# regelschaltplan.net
KiCad netlist of a schematic drawn in EAGLE
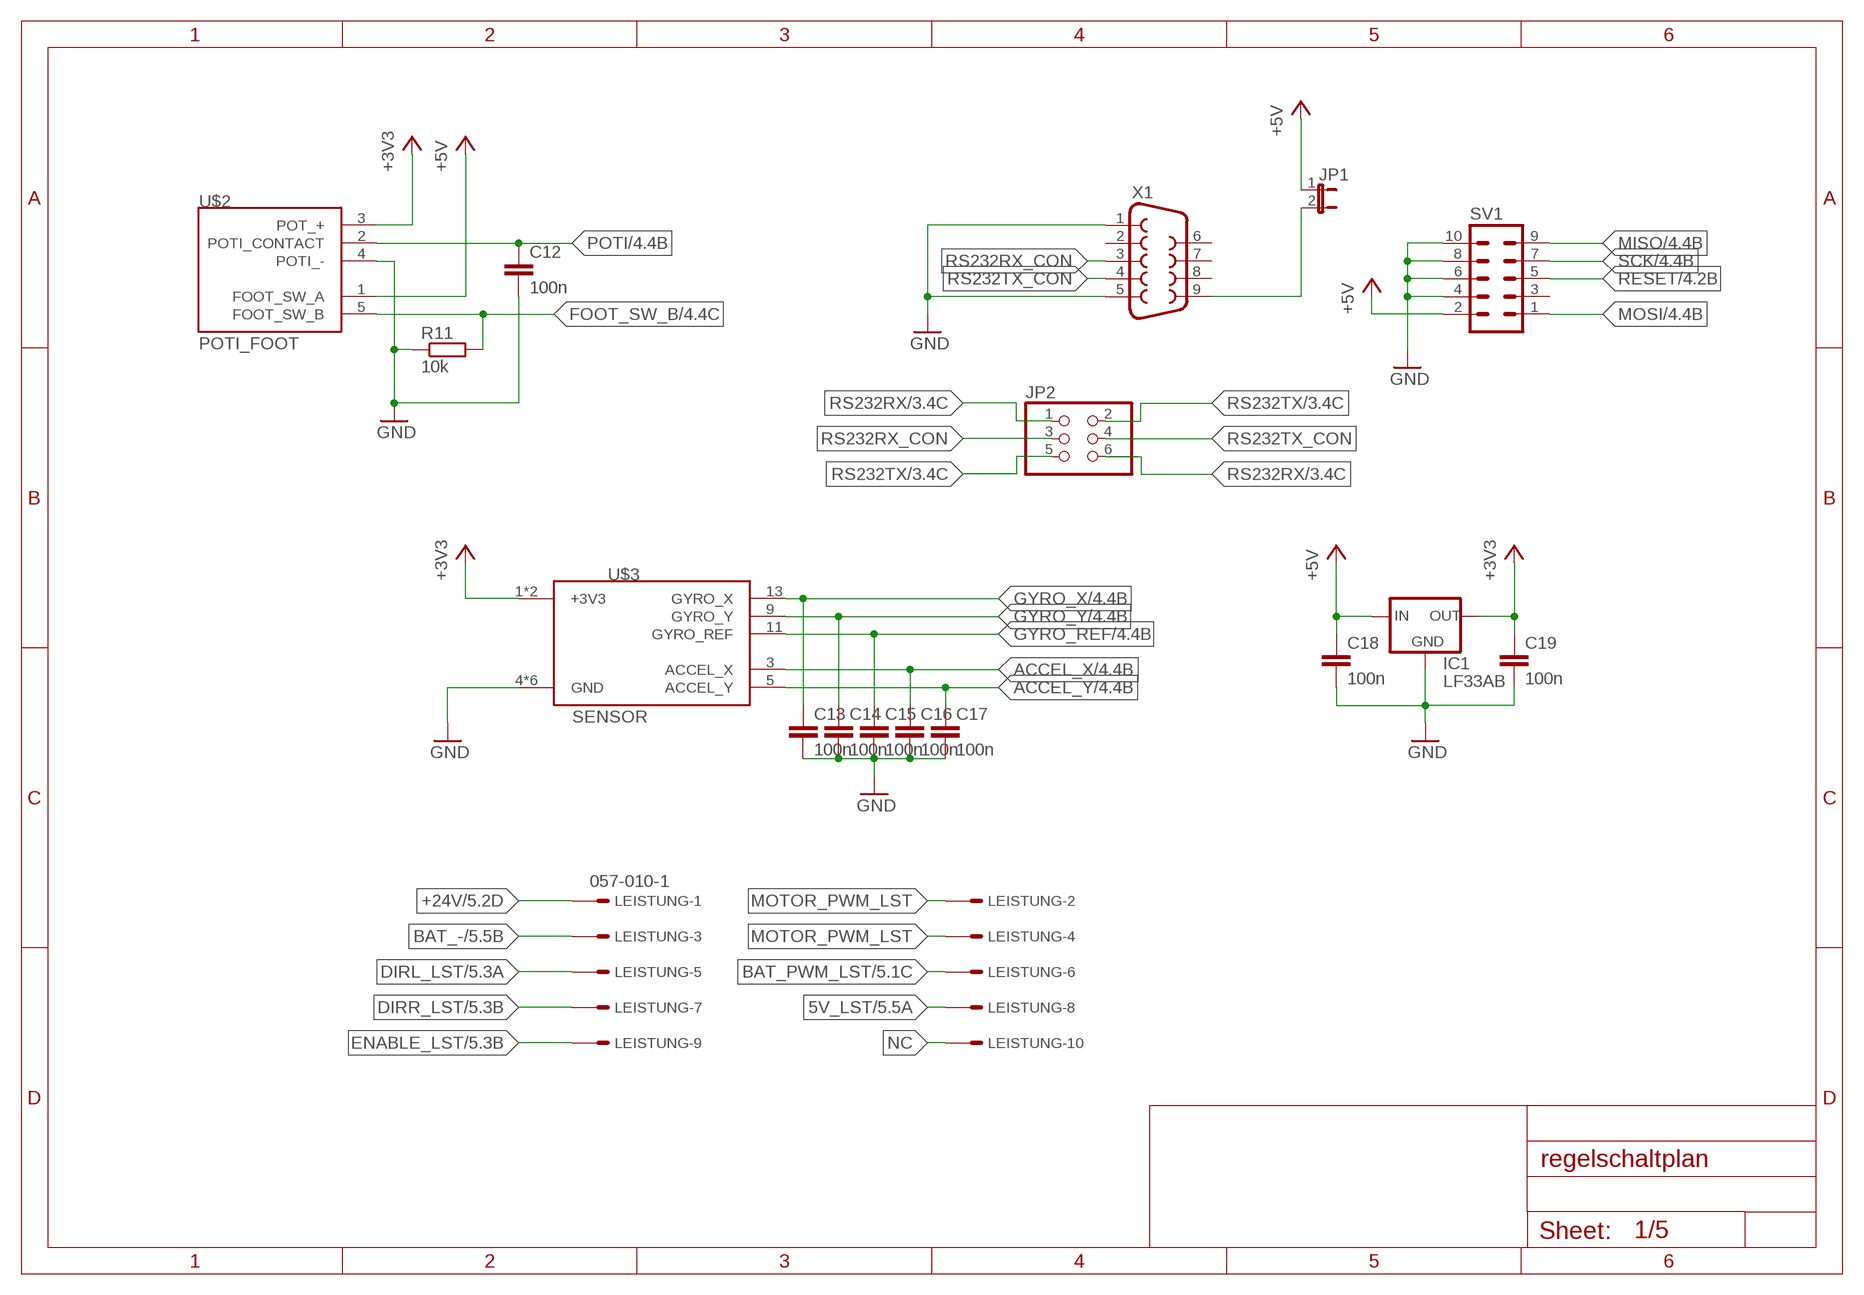
[diagram p0: schematic, sheet 1]
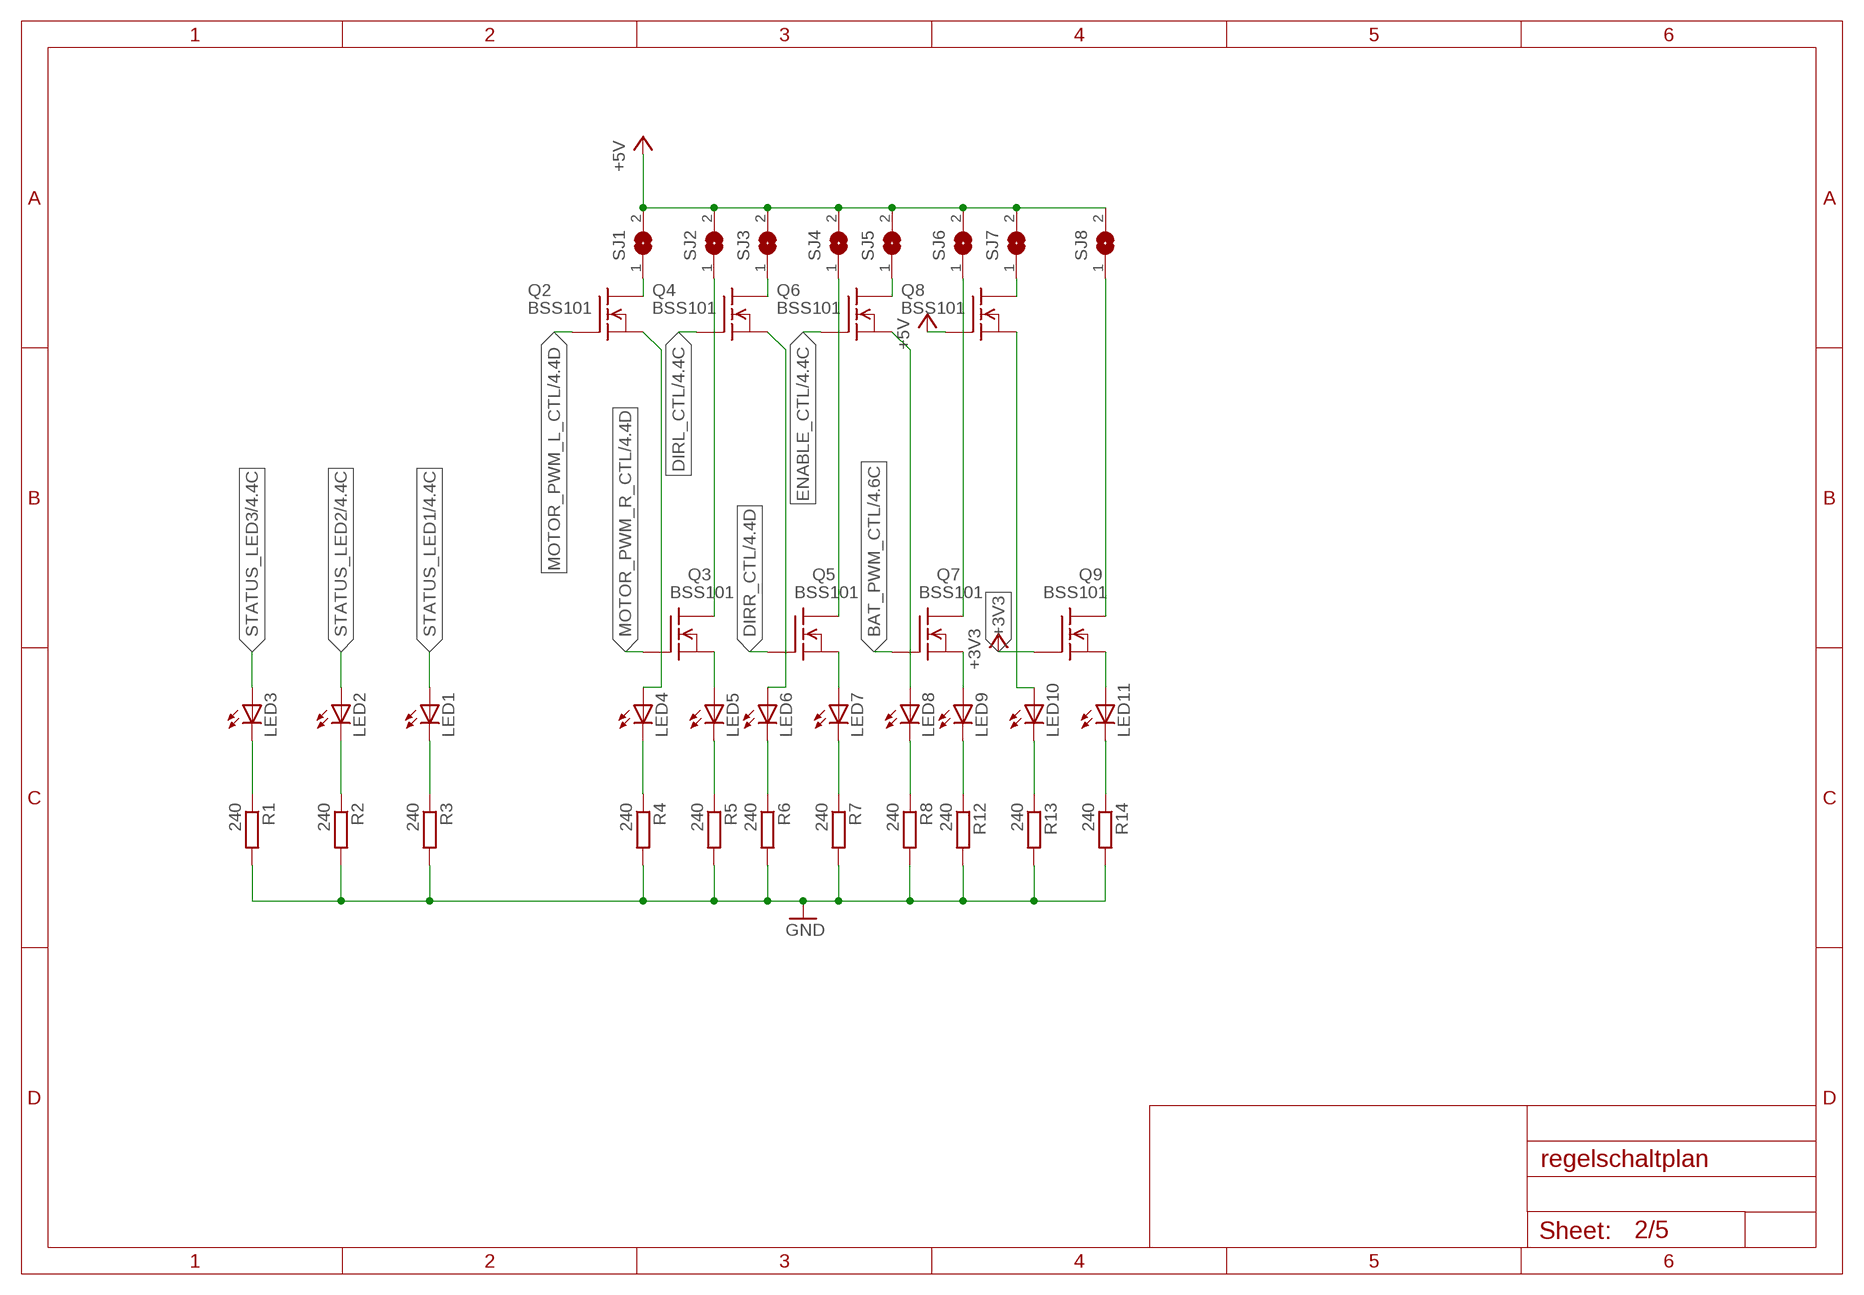
[diagram p1: schematic, sheet 2]
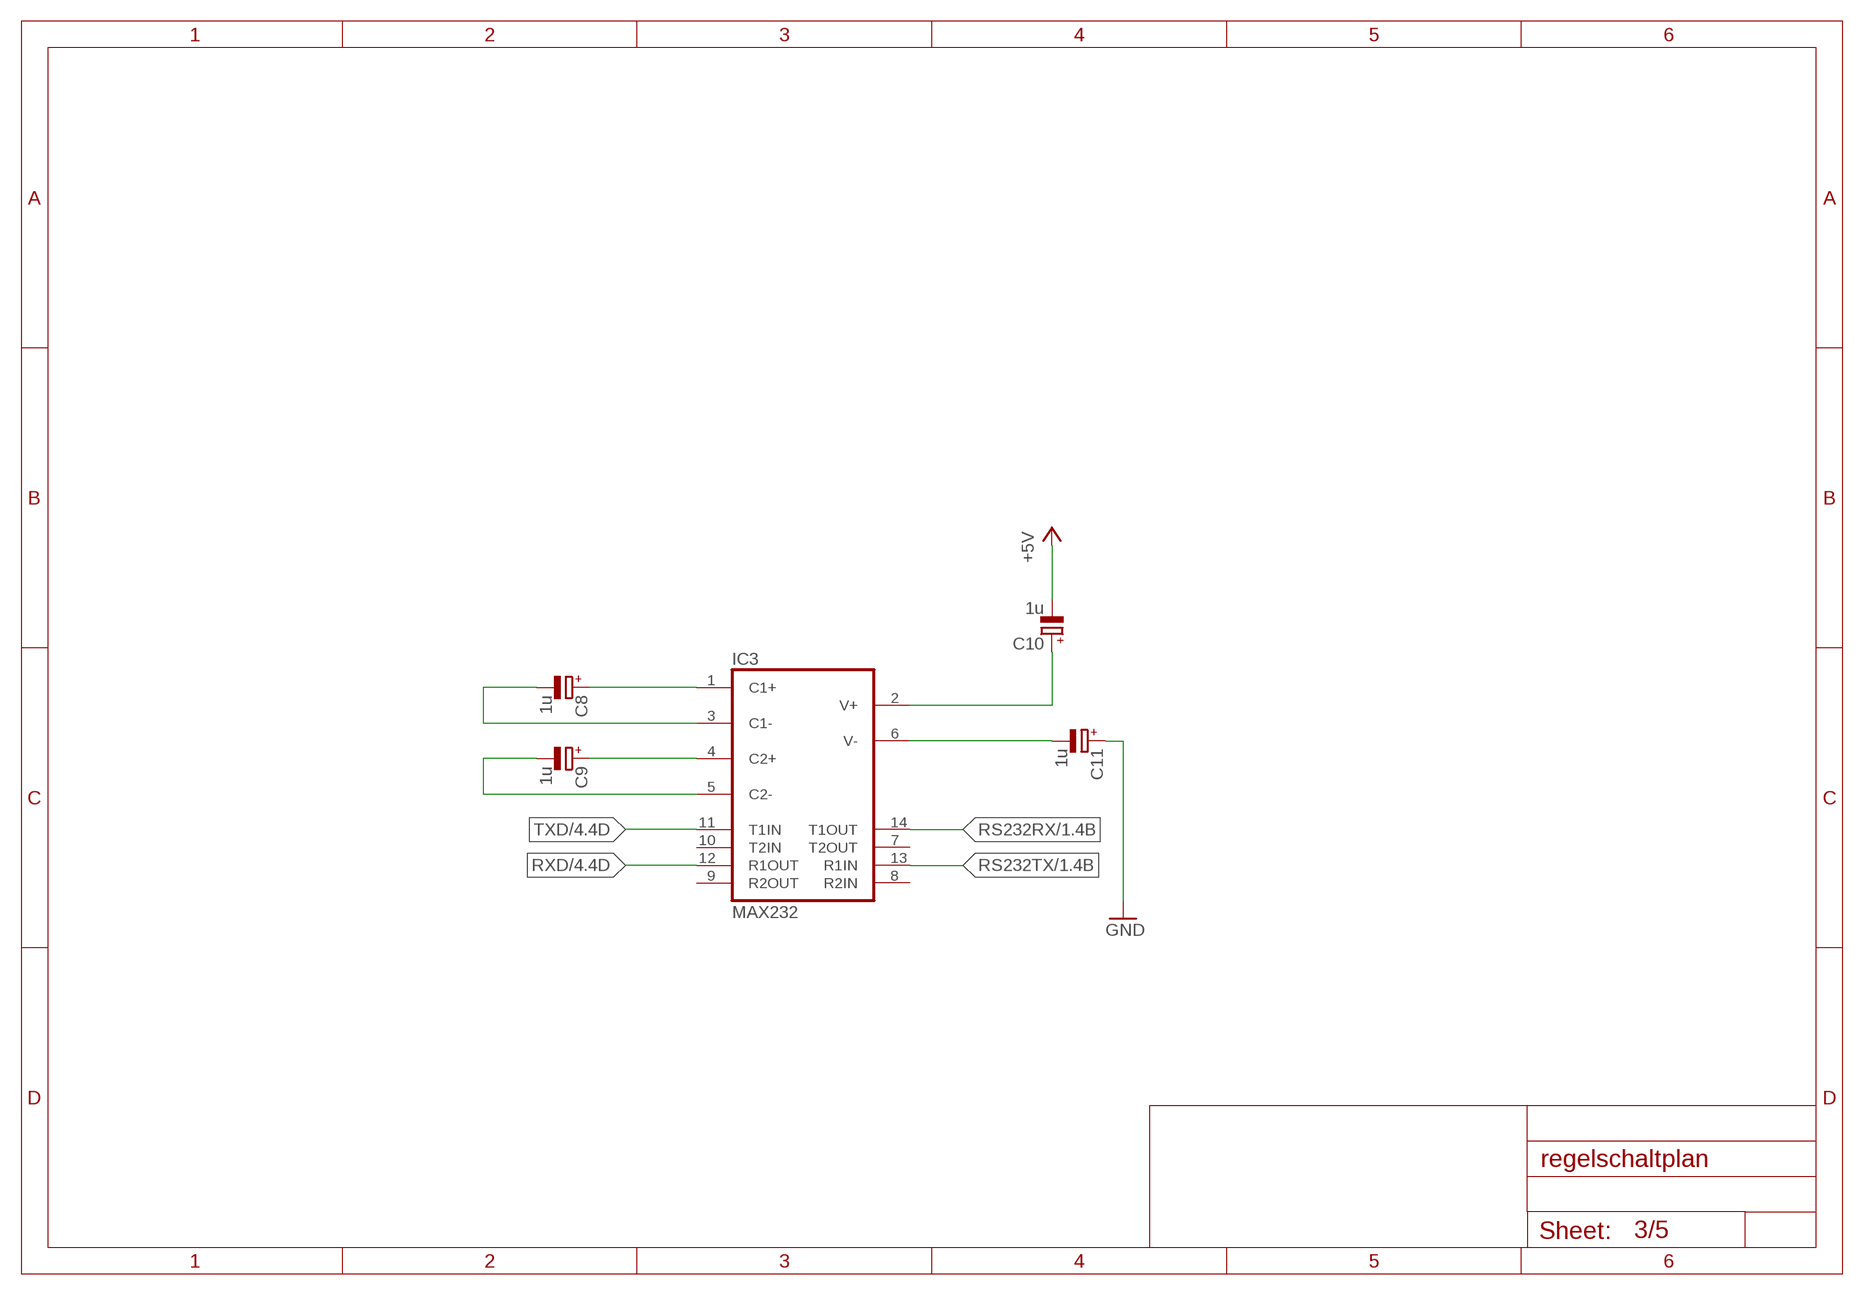
[diagram p2: schematic, sheet 3]
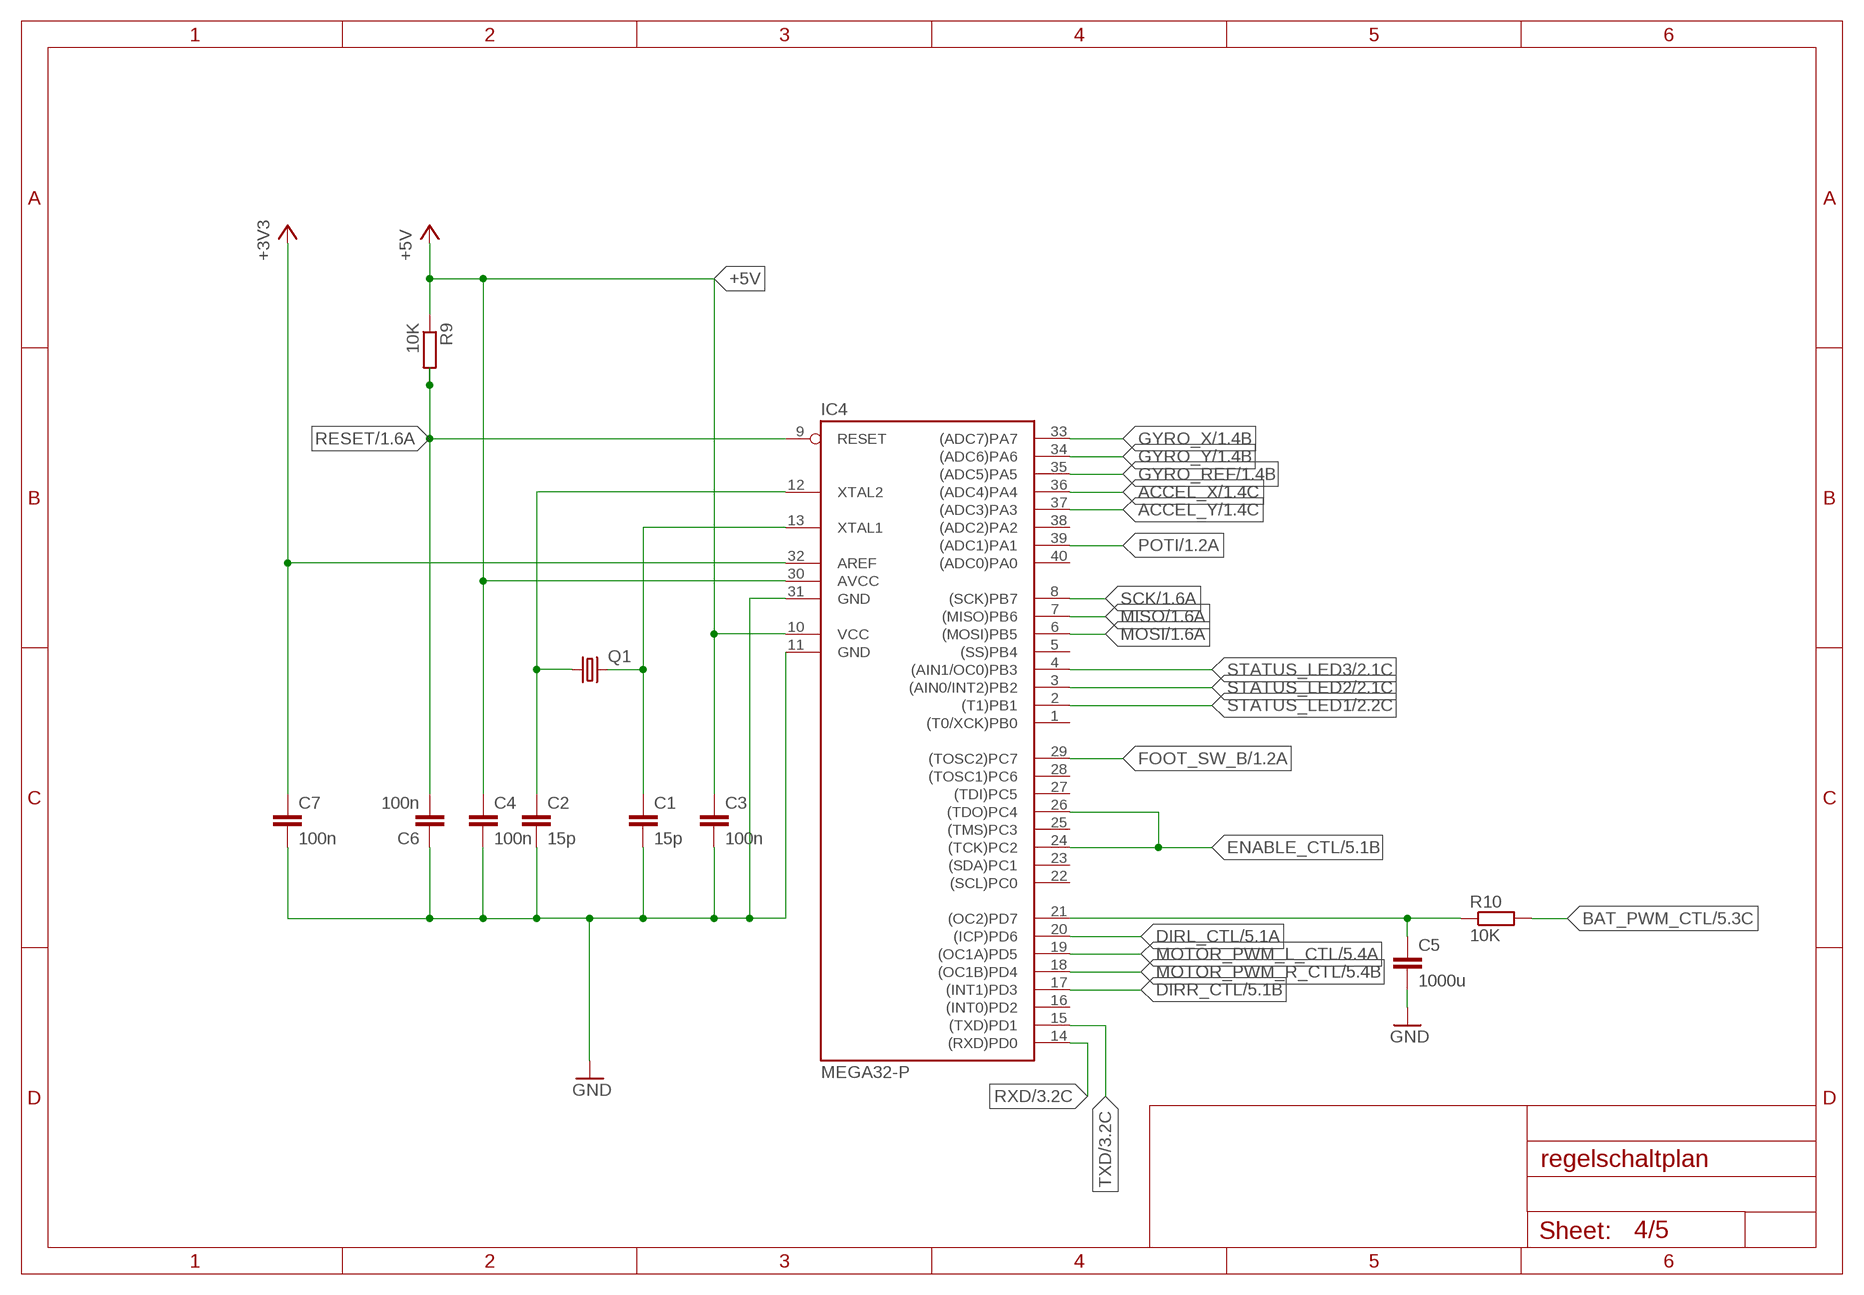
[diagram p3: schematic, sheet 4]
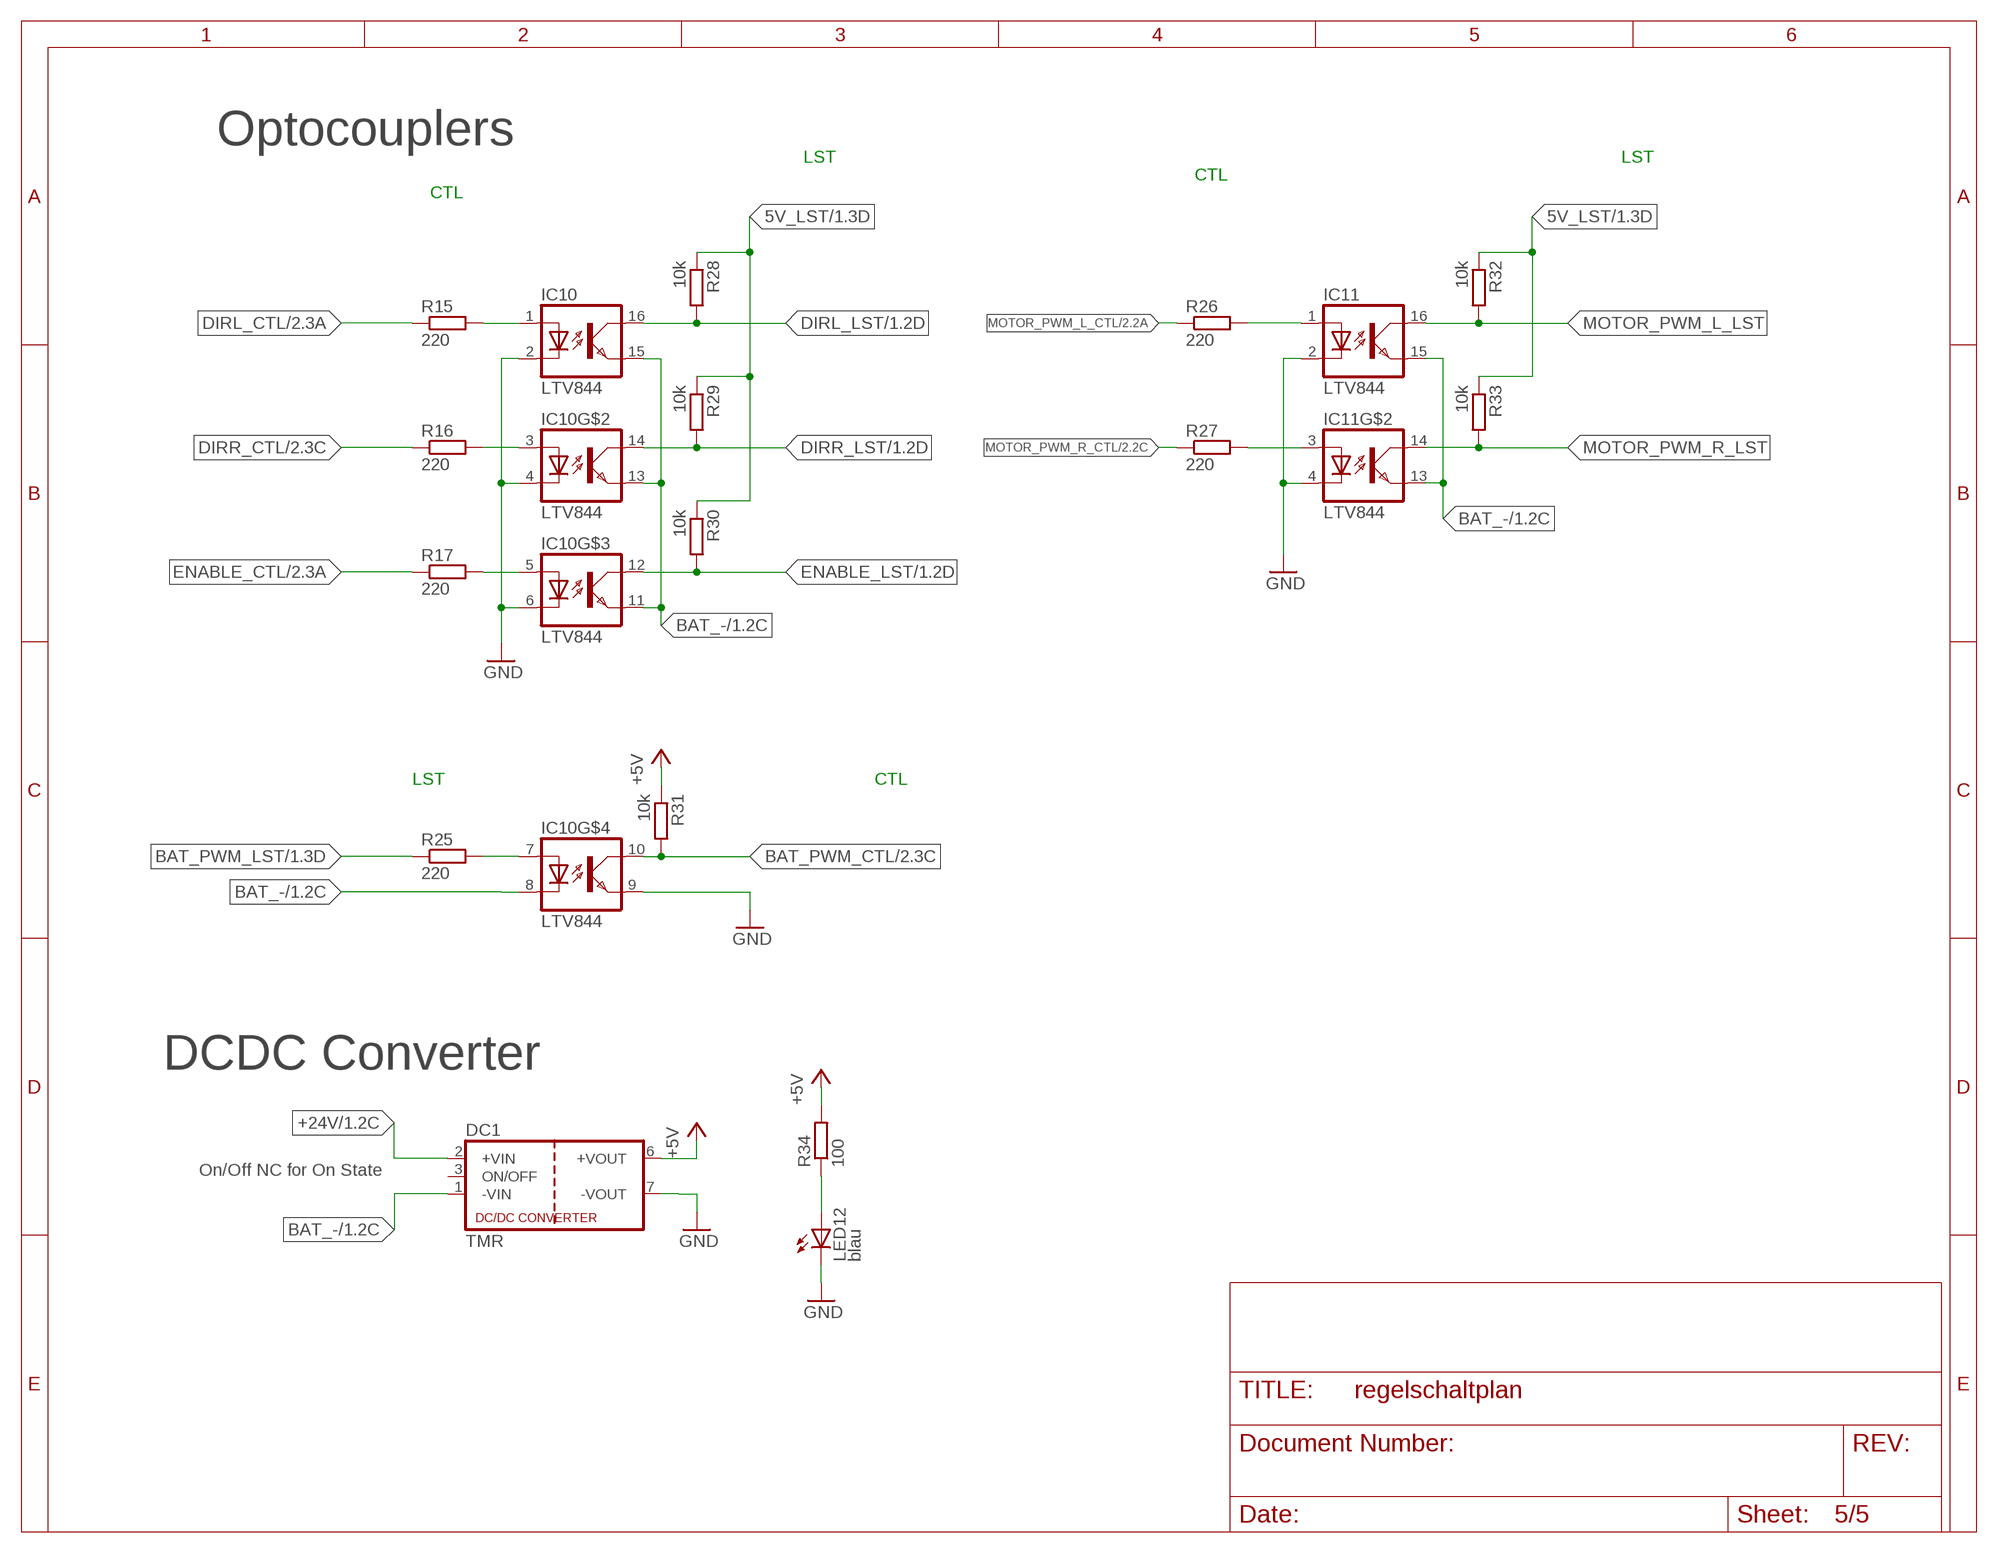
[diagram p4: schematic, sheet 5]

(export (version "E")
  (design (tool "Eeschema 10.0.6"))
  (components
    (comp (ref "C12")
      (value "100n")
      (footprint "eagle-import:C025-025X050")
      (libsource (lib "eagle-import") (part "C-EU025-025X050"))
    )
    (comp (ref "C13")
      (value "100n")
      (footprint "eagle-import:C025-025X050")
      (libsource (lib "eagle-import") (part "C-EU025-025X050"))
    )
    (comp (ref "C14")
      (value "100n")
      (footprint "eagle-import:C025-025X050")
      (libsource (lib "eagle-import") (part "C-EU025-025X050"))
    )
    (comp (ref "C15")
      (value "100n")
      (footprint "eagle-import:C025-025X050")
      (libsource (lib "eagle-import") (part "C-EU025-025X050"))
    )
    (comp (ref "C16")
      (value "100n")
      (footprint "eagle-import:C025-025X050")
      (libsource (lib "eagle-import") (part "C-EU025-025X050"))
    )
    (comp (ref "C17")
      (value "100n")
      (footprint "eagle-import:C025-025X050")
      (libsource (lib "eagle-import") (part "C-EU025-025X050"))
    )
    (comp (ref "C18")
      (value "100n")
      (footprint "eagle-import:C025-025X050")
      (libsource (lib "eagle-import") (part "C-EU025-025X050"))
    )
    (comp (ref "C19")
      (value "100n")
      (footprint "eagle-import:C025-025X050")
      (libsource (lib "eagle-import") (part "C-EU025-025X050"))
    )
    (comp (ref "IC1")
      (value "LF33AB")
      (footprint "eagle-import:TO220")
      (libsource (lib "eagle-import") (part "LF33AB"))
    )
    (comp (ref "JP1")
      (value "JP1E")
      (footprint "eagle-import:JP1")
      (libsource (lib "eagle-import") (part "JP1E"))
    )
    (comp (ref "JP2")
      (value "PINHD-2X3")
      (footprint "eagle-import:2X03")
      (libsource (lib "eagle-import") (part "PINHD-2X3"))
    )
    (comp (ref "LEISTUNG")
      (value "057-010-1")
      (footprint "eagle-import:057-010-1")
      (libsource (lib "eagle-import") (part "057-010-1"))
    )
    (comp (ref "R11")
      (value "10k")
      (footprint "eagle-import:0207_7")
      (libsource (lib "eagle-import") (part "R-EU_0207/7"))
    )
    (comp (ref "SV1")
      (value "MA05-2")
      (footprint "eagle-import:MA05-2")
      (libsource (lib "eagle-import") (part "MA05-2"))
    )
    (comp (ref "U$2")
      (value "POTI_FOOT")
      (footprint "eagle-import:CON_6")
      (libsource (lib "eagle-import") (part "POTI_FOOT"))
    )
    (comp (ref "U$3")
      (value "SENSOR")
      (footprint "eagle-import:CON_14")
      (libsource (lib "eagle-import") (part "SENSOR"))
    )
    (comp (ref "X1")
      (value "F09HP")
      (footprint "eagle-import:F09HP")
      (libsource (lib "eagle-import") (part "F09HP"))
    )
    (comp (ref "LED1")
      (value "LED3MM")
      (footprint "eagle-import:LED3MM")
      (libsource (lib "eagle-import") (part "LED3MM"))
    )
    (comp (ref "LED2")
      (value "LED3MM")
      (footprint "eagle-import:LED3MM")
      (libsource (lib "eagle-import") (part "LED3MM"))
    )
    (comp (ref "LED3")
      (value "LED3MM")
      (footprint "eagle-import:LED3MM")
      (libsource (lib "eagle-import") (part "LED3MM"))
    )
    (comp (ref "LED4")
      (value "LED3MM")
      (footprint "eagle-import:LED3MM")
      (libsource (lib "eagle-import") (part "LED3MM"))
    )
    (comp (ref "LED5")
      (value "LED3MM")
      (footprint "eagle-import:LED3MM")
      (libsource (lib "eagle-import") (part "LED3MM"))
    )
    (comp (ref "LED6")
      (value "LED3MM")
      (footprint "eagle-import:LED3MM")
      (libsource (lib "eagle-import") (part "LED3MM"))
    )
    (comp (ref "LED7")
      (value "LED3MM")
      (footprint "eagle-import:LED3MM")
      (libsource (lib "eagle-import") (part "LED3MM"))
    )
    (comp (ref "LED8")
      (value "LED3MM")
      (footprint "eagle-import:LED3MM")
      (libsource (lib "eagle-import") (part "LED3MM"))
    )
    (comp (ref "LED9")
      (value "LED3MM")
      (footprint "eagle-import:LED3MM")
      (libsource (lib "eagle-import") (part "LED3MM"))
    )
    (comp (ref "LED10")
      (value "LED3MM")
      (footprint "eagle-import:LED3MM")
      (libsource (lib "eagle-import") (part "LED3MM"))
    )
    (comp (ref "LED11")
      (value "LED3MM")
      (footprint "eagle-import:LED3MM")
      (libsource (lib "eagle-import") (part "LED3MM"))
    )
    (comp (ref "Q2")
      (value "BSS101")
      (footprint "eagle-import:TO92")
      (libsource (lib "eagle-import") (part "BSS101"))
    )
    (comp (ref "Q3")
      (value "BSS101")
      (footprint "eagle-import:TO92")
      (libsource (lib "eagle-import") (part "BSS101"))
    )
    (comp (ref "Q4")
      (value "BSS101")
      (footprint "eagle-import:TO92")
      (libsource (lib "eagle-import") (part "BSS101"))
    )
    (comp (ref "Q5")
      (value "BSS101")
      (footprint "eagle-import:TO92")
      (libsource (lib "eagle-import") (part "BSS101"))
    )
    (comp (ref "Q6")
      (value "BSS101")
      (footprint "eagle-import:TO92")
      (libsource (lib "eagle-import") (part "BSS101"))
    )
    (comp (ref "Q7")
      (value "BSS101")
      (footprint "eagle-import:TO92")
      (libsource (lib "eagle-import") (part "BSS101"))
    )
    (comp (ref "Q8")
      (value "BSS101")
      (footprint "eagle-import:TO92")
      (libsource (lib "eagle-import") (part "BSS101"))
    )
    (comp (ref "Q9")
      (value "BSS101")
      (footprint "eagle-import:TO92")
      (libsource (lib "eagle-import") (part "BSS101"))
    )
    (comp (ref "R1")
      (value "240")
      (footprint "eagle-import:0207_7")
      (libsource (lib "eagle-import") (part "R-EU_0207/7"))
    )
    (comp (ref "R2")
      (value "240")
      (footprint "eagle-import:0207_7")
      (libsource (lib "eagle-import") (part "R-EU_0207/7"))
    )
    (comp (ref "R3")
      (value "240")
      (footprint "eagle-import:0207_7")
      (libsource (lib "eagle-import") (part "R-EU_0207/7"))
    )
    (comp (ref "R4")
      (value "240")
      (footprint "eagle-import:0207_7")
      (libsource (lib "eagle-import") (part "R-EU_0207/7"))
    )
    (comp (ref "R5")
      (value "240")
      (footprint "eagle-import:0207_7")
      (libsource (lib "eagle-import") (part "R-EU_0207/7"))
    )
    (comp (ref "R6")
      (value "240")
      (footprint "eagle-import:0207_7")
      (libsource (lib "eagle-import") (part "R-EU_0207/7"))
    )
    (comp (ref "R7")
      (value "240")
      (footprint "eagle-import:0207_7")
      (libsource (lib "eagle-import") (part "R-EU_0207/7"))
    )
    (comp (ref "R8")
      (value "240")
      (footprint "eagle-import:0207_7")
      (libsource (lib "eagle-import") (part "R-EU_0207/7"))
    )
    (comp (ref "R12")
      (value "240")
      (footprint "eagle-import:0207_7")
      (libsource (lib "eagle-import") (part "R-EU_0207/7"))
    )
    (comp (ref "R13")
      (value "240")
      (footprint "eagle-import:0207_7")
      (libsource (lib "eagle-import") (part "R-EU_0207/7"))
    )
    (comp (ref "R14")
      (value "240")
      (footprint "eagle-import:0207_7")
      (libsource (lib "eagle-import") (part "R-EU_0207/7"))
    )
    (comp (ref "SJ1") (value "SJ") (footprint "eagle-import:SJ") (libsource (lib "eagle-import") (part "SJ")))
    (comp (ref "SJ2") (value "SJ") (footprint "eagle-import:SJ") (libsource (lib "eagle-import") (part "SJ")))
    (comp (ref "SJ3") (value "SJ") (footprint "eagle-import:SJ") (libsource (lib "eagle-import") (part "SJ")))
    (comp (ref "SJ4") (value "SJ") (footprint "eagle-import:SJ") (libsource (lib "eagle-import") (part "SJ")))
    (comp (ref "SJ5") (value "SJ") (footprint "eagle-import:SJ") (libsource (lib "eagle-import") (part "SJ")))
    (comp (ref "SJ6") (value "SJ") (footprint "eagle-import:SJ") (libsource (lib "eagle-import") (part "SJ")))
    (comp (ref "SJ7") (value "SJ") (footprint "eagle-import:SJ") (libsource (lib "eagle-import") (part "SJ")))
    (comp (ref "SJ8") (value "SJ") (footprint "eagle-import:SJ") (libsource (lib "eagle-import") (part "SJ")))
    (comp (ref "C8")
      (value "1u")
      (footprint "eagle-import:E2,5-6E")
      (libsource (lib "eagle-import") (part "CPOL-EUE2,5-6E"))
    )
    (comp (ref "C9")
      (value "1u")
      (footprint "eagle-import:E2,5-6E")
      (libsource (lib "eagle-import") (part "CPOL-EUE2,5-6E"))
    )
    (comp (ref "C10")
      (value "1u")
      (footprint "eagle-import:E2,5-6E")
      (libsource (lib "eagle-import") (part "CPOL-EUE2,5-6E"))
    )
    (comp (ref "C11")
      (value "1u")
      (footprint "eagle-import:E2,5-6E")
      (libsource (lib "eagle-import") (part "CPOL-EUE2,5-6E"))
    )
    (comp (ref "IC3")
      (value "MAX232")
      (footprint "eagle-import:DIL16")
      (fields (field (name "MF") "MAXIM") (field (name "MPN") "MAX232ACPE+"))
      (libsource (lib "eagle-import") (part "MAX232"))
    )
    (comp (ref "DC1")
      (value "TMR")
      (footprint "eagle-import:TRACO_SIP-8")
      (libsource (lib "eagle-import") (part "TMR"))
    )
    (comp (ref "IC10")
      (value "LTV844")
      (footprint "eagle-import:DIL16")
      (libsource (lib "eagle-import") (part "LTV844"))
    )
    (comp (ref "IC11")
      (value "LTV844")
      (footprint "eagle-import:DIL16")
      (libsource (lib "eagle-import") (part "LTV844"))
    )
    (comp (ref "LED12")
      (value "blau")
      (footprint "eagle-import:LED3MM")
      (libsource (lib "eagle-import") (part "LED3MM"))
    )
    (comp (ref "R15")
      (value "220")
      (footprint "eagle-import:0207_10")
      (libsource (lib "eagle-import") (part "R-EU_0207/10"))
    )
    (comp (ref "R16")
      (value "220")
      (footprint "eagle-import:0207_10")
      (libsource (lib "eagle-import") (part "R-EU_0207/10"))
    )
    (comp (ref "R17")
      (value "220")
      (footprint "eagle-import:0207_10")
      (libsource (lib "eagle-import") (part "R-EU_0207/10"))
    )
    (comp (ref "R25")
      (value "220")
      (footprint "eagle-import:0207_10")
      (libsource (lib "eagle-import") (part "R-EU_0207/10"))
    )
    (comp (ref "R26")
      (value "220")
      (footprint "eagle-import:0207_10")
      (libsource (lib "eagle-import") (part "R-EU_0207/10"))
    )
    (comp (ref "R27")
      (value "220")
      (footprint "eagle-import:0207_10")
      (libsource (lib "eagle-import") (part "R-EU_0207/10"))
    )
    (comp (ref "R28")
      (value "10k")
      (footprint "eagle-import:0207_10")
      (libsource (lib "eagle-import") (part "R-EU_0207/10"))
    )
    (comp (ref "R29")
      (value "10k")
      (footprint "eagle-import:0207_10")
      (libsource (lib "eagle-import") (part "R-EU_0207/10"))
    )
    (comp (ref "R30")
      (value "10k")
      (footprint "eagle-import:0207_10")
      (libsource (lib "eagle-import") (part "R-EU_0207/10"))
    )
    (comp (ref "R31")
      (value "10k")
      (footprint "eagle-import:0207_10")
      (libsource (lib "eagle-import") (part "R-EU_0207/10"))
    )
    (comp (ref "R32")
      (value "10k")
      (footprint "eagle-import:0207_10")
      (libsource (lib "eagle-import") (part "R-EU_0207/10"))
    )
    (comp (ref "R33")
      (value "10k")
      (footprint "eagle-import:0207_10")
      (libsource (lib "eagle-import") (part "R-EU_0207/10"))
    )
    (comp (ref "R34")
      (value "100")
      (footprint "eagle-import:0207_10")
      (libsource (lib "eagle-import") (part "R-EU_0207/10"))
    )
    (comp (ref "C1")
      (value "15p")
      (footprint "eagle-import:C025-025X050")
      (libsource (lib "eagle-import") (part "C-EU025-025X050"))
    )
    (comp (ref "C2")
      (value "15p")
      (footprint "eagle-import:C025-025X050")
      (libsource (lib "eagle-import") (part "C-EU025-025X050"))
    )
    (comp (ref "C3")
      (value "100n")
      (footprint "eagle-import:C025-025X050")
      (libsource (lib "eagle-import") (part "C-EU025-025X050"))
    )
    (comp (ref "C4")
      (value "100n")
      (footprint "eagle-import:C025-025X050")
      (libsource (lib "eagle-import") (part "C-EU025-025X050"))
    )
    (comp (ref "C5")
      (value "1000u")
      (footprint "eagle-import:C025-025X050")
      (libsource (lib "eagle-import") (part "C-EU025-025X050"))
    )
    (comp (ref "C6")
      (value "100n")
      (footprint "eagle-import:C025-025X050")
      (libsource (lib "eagle-import") (part "C-EU025-025X050"))
    )
    (comp (ref "C7")
      (value "100n")
      (footprint "eagle-import:C025-025X050")
      (libsource (lib "eagle-import") (part "C-EU025-025X050"))
    )
    (comp (ref "IC4")
      (value "MEGA32-P")
      (footprint "eagle-import:DIL40")
      (fields (field (name "MPN") "ATMEGA32-16PU"))
      (libsource (lib "eagle-import") (part "MEGA32-P"))
    )
    (comp (ref "Q1")
      (value "CRYSTALHC49U-V")
      (footprint "eagle-import:HC49U-V")
      (libsource (lib "eagle-import") (part "CRYSTALHC49U-V"))
    )
    (comp (ref "R9")
      (value "10K")
      (footprint "eagle-import:0207_7")
      (libsource (lib "eagle-import") (part "R-EU_0207/7"))
    )
    (comp (ref "R10")
      (value "10K")
      (footprint "eagle-import:0207_7")
      (libsource (lib "eagle-import") (part "R-EU_0207/7"))
    )
  )
  (nets
    (net (code "1") (name "+3V3") (class "Default")
      (node (ref "C19") (pin "1") (pinfunction "1_1") (pintype "passive"))
      (node (ref "C7") (pin "1") (pinfunction "1_1") (pintype "passive"))
      (node (ref "IC1") (pin "3") (pinfunction "OUT_3") (pintype "passive"))
      (node (ref "IC4") (pin "32") (pinfunction "AREF_32") (pintype "passive"))
      (node (ref "Q9") (pin "2") (pinfunction "G_2") (pintype "passive"))
      (node (ref "U$2") (pin "3") (pinfunction "POT_+_3") (pintype "power_in"))
      (node (ref "U$3") (pin "1") (pinfunction "+3V3_1") (pintype "power_in"))
      (node (ref "U$3") (pin "2") (pinfunction "+3V3_2") (pintype "power_in"))
    )
    (net (code "2") (name "+5V") (class "Default")
      (node (ref "C10") (pin "-") (pinfunction "-_-") (pintype "passive"))
      (node (ref "C18") (pin "1") (pinfunction "1_1") (pintype "passive"))
      (node (ref "C3") (pin "1") (pinfunction "1_1") (pintype "passive"))
      (node (ref "C4") (pin "1") (pinfunction "1_1") (pintype "passive"))
      (node (ref "DC1") (pin "6") (pinfunction "+VOUT_6") (pintype "passive"))
      (node (ref "IC1") (pin "1") (pinfunction "IN_1") (pintype "input"))
      (node (ref "IC4") (pin "10") (pinfunction "VCC_10") (pintype "power_in"))
      (node (ref "IC4") (pin "30") (pinfunction "AVCC_30") (pintype "power_in"))
      (node (ref "JP1") (pin "1") (pinfunction "1_1") (pintype "passive"))
      (node (ref "Q8") (pin "2") (pinfunction "G_2") (pintype "passive"))
      (node (ref "R31") (pin "1") (pinfunction "1_1") (pintype "passive"))
      (node (ref "R34") (pin "2") (pinfunction "2_2") (pintype "passive"))
      (node (ref "R9") (pin "1") (pinfunction "1_1") (pintype "passive"))
      (node (ref "SJ1") (pin "2") (pinfunction "2_2") (pintype "passive"))
      (node (ref "SJ2") (pin "2") (pinfunction "2_2") (pintype "passive"))
      (node (ref "SJ3") (pin "2") (pinfunction "2_2") (pintype "passive"))
      (node (ref "SJ4") (pin "2") (pinfunction "2_2") (pintype "passive"))
      (node (ref "SJ5") (pin "2") (pinfunction "2_2") (pintype "passive"))
      (node (ref "SJ6") (pin "2") (pinfunction "2_2") (pintype "passive"))
      (node (ref "SJ7") (pin "2") (pinfunction "2_2") (pintype "passive"))
      (node (ref "SJ8") (pin "2") (pinfunction "2_2") (pintype "passive"))
      (node (ref "SV1") (pin "2") (pinfunction "2_2") (pintype "passive"))
      (node (ref "U$2") (pin "1") (pinfunction "FOOT_SW_A_1") (pintype "bidirectional"))
    )
    (net (code "3") (name "+24V") (class "Default")
      (node (ref "DC1") (pin "2") (pinfunction "+VIN_2") (pintype "passive"))
      (node (ref "LEISTUNG") (pin "1") (pinfunction "S_1") (pintype "passive"))
    )
    (net (code "4") (name "5V_LST") (class "Default")
      (node (ref "LEISTUNG") (pin "8") (pinfunction "S_8") (pintype "passive"))
      (node (ref "R28") (pin "1") (pinfunction "1_1") (pintype "passive"))
      (node (ref "R29") (pin "1") (pinfunction "1_1") (pintype "passive"))
      (node (ref "R30") (pin "1") (pinfunction "1_1") (pintype "passive"))
      (node (ref "R32") (pin "1") (pinfunction "1_1") (pintype "passive"))
      (node (ref "R33") (pin "1") (pinfunction "1_1") (pintype "passive"))
    )
    (net (code "5") (name "ACCEL_X") (class "Default")
      (node (ref "C16") (pin "1") (pinfunction "1_1") (pintype "passive"))
      (node (ref "IC4") (pin "36") (pinfunction "(ADC4)PA4_36") (pintype "bidirectional"))
      (node (ref "U$3") (pin "3") (pinfunction "ACCEL_X_3") (pintype "output"))
    )
    (net (code "6") (name "ACCEL_Y") (class "Default")
      (node (ref "C17") (pin "1") (pinfunction "1_1") (pintype "passive"))
      (node (ref "IC4") (pin "37") (pinfunction "(ADC3)PA3_37") (pintype "bidirectional"))
      (node (ref "U$3") (pin "5") (pinfunction "ACCEL_Y_5") (pintype "output"))
    )
    (net (code "7") (name "BAT_-") (class "Default")
      (node (ref "DC1") (pin "1") (pinfunction "-VIN_1") (pintype "passive"))
      (node (ref "IC10") (pin "11") (pinfunction "EMIT_11") (pintype "passive"))
      (node (ref "IC10") (pin "13") (pinfunction "EMIT_13") (pintype "passive"))
      (node (ref "IC10") (pin "15") (pinfunction "EMIT_15") (pintype "passive"))
      (node (ref "IC10") (pin "8") (pinfunction "C_8") (pintype "passive"))
      (node (ref "IC11") (pin "13") (pinfunction "EMIT_13") (pintype "passive"))
      (node (ref "IC11") (pin "15") (pinfunction "EMIT_15") (pintype "passive"))
      (node (ref "LEISTUNG") (pin "3") (pinfunction "S_3") (pintype "passive"))
    )
    (net (code "8") (name "BAT_PWM_CTL") (class "Default")
      (node (ref "IC10") (pin "10") (pinfunction "COL_10") (pintype "passive"))
      (node (ref "Q7") (pin "2") (pinfunction "G_2") (pintype "passive"))
      (node (ref "R10") (pin "2") (pinfunction "2_2") (pintype "passive"))
      (node (ref "R31") (pin "2") (pinfunction "2_2") (pintype "passive"))
    )
    (net (code "9") (name "BAT_PWM_LST") (class "Default")
      (node (ref "LEISTUNG") (pin "6") (pinfunction "S_6") (pintype "passive"))
      (node (ref "R25") (pin "1") (pinfunction "1_1") (pintype "passive"))
    )
    (net (code "10") (name "DIRL_CTL") (class "Default")
      (node (ref "IC4") (pin "20") (pinfunction "(ICP)PD6_20") (pintype "bidirectional"))
      (node (ref "Q4") (pin "2") (pinfunction "G_2") (pintype "passive"))
      (node (ref "R15") (pin "1") (pinfunction "1_1") (pintype "passive"))
    )
    (net (code "11") (name "DIRL_LST") (class "Default")
      (node (ref "IC10") (pin "16") (pinfunction "COL_16") (pintype "passive"))
      (node (ref "LEISTUNG") (pin "5") (pinfunction "S_5") (pintype "passive"))
      (node (ref "R28") (pin "2") (pinfunction "2_2") (pintype "passive"))
    )
    (net (code "12") (name "DIRR_CTL") (class "Default")
      (node (ref "IC4") (pin "17") (pinfunction "(INT1)PD3_17") (pintype "bidirectional"))
      (node (ref "Q5") (pin "2") (pinfunction "G_2") (pintype "passive"))
      (node (ref "R16") (pin "1") (pinfunction "1_1") (pintype "passive"))
    )
    (net (code "13") (name "DIRR_LST") (class "Default")
      (node (ref "IC10") (pin "14") (pinfunction "COL_14") (pintype "passive"))
      (node (ref "LEISTUNG") (pin "7") (pinfunction "S_7") (pintype "passive"))
      (node (ref "R29") (pin "2") (pinfunction "2_2") (pintype "passive"))
    )
    (net (code "14") (name "ENABLE_CTL") (class "Default")
      (node (ref "IC4") (pin "24") (pinfunction "(TCK)PC2_24") (pintype "bidirectional"))
      (node (ref "IC4") (pin "26") (pinfunction "(TDO)PC4_26") (pintype "bidirectional"))
      (node (ref "Q6") (pin "2") (pinfunction "G_2") (pintype "passive"))
      (node (ref "R17") (pin "1") (pinfunction "1_1") (pintype "passive"))
    )
    (net (code "15") (name "ENABLE_LST") (class "Default")
      (node (ref "IC10") (pin "12") (pinfunction "COL_12") (pintype "passive"))
      (node (ref "LEISTUNG") (pin "9") (pinfunction "S_9") (pintype "passive"))
      (node (ref "R30") (pin "2") (pinfunction "2_2") (pintype "passive"))
    )
    (net (code "16") (name "FOOT_SW_B") (class "Default")
      (node (ref "IC4") (pin "29") (pinfunction "(TOSC2)PC7_29") (pintype "bidirectional"))
      (node (ref "R11") (pin "2") (pinfunction "2_2") (pintype "passive"))
      (node (ref "U$2") (pin "5") (pinfunction "FOOT_SW_B_5") (pintype "bidirectional"))
    )
    (net (code "17") (name "GND") (class "Default")
      (node (ref "C1") (pin "2") (pinfunction "2_2") (pintype "passive"))
      (node (ref "C11") (pin "+") (pinfunction "+_+") (pintype "passive"))
      (node (ref "C12") (pin "2") (pinfunction "2_2") (pintype "passive"))
      (node (ref "C13") (pin "2") (pinfunction "2_2") (pintype "passive"))
      (node (ref "C14") (pin "2") (pinfunction "2_2") (pintype "passive"))
      (node (ref "C15") (pin "2") (pinfunction "2_2") (pintype "passive"))
      (node (ref "C16") (pin "2") (pinfunction "2_2") (pintype "passive"))
      (node (ref "C17") (pin "2") (pinfunction "2_2") (pintype "passive"))
      (node (ref "C18") (pin "2") (pinfunction "2_2") (pintype "passive"))
      (node (ref "C19") (pin "2") (pinfunction "2_2") (pintype "passive"))
      (node (ref "C2") (pin "2") (pinfunction "2_2") (pintype "passive"))
      (node (ref "C3") (pin "2") (pinfunction "2_2") (pintype "passive"))
      (node (ref "C4") (pin "2") (pinfunction "2_2") (pintype "passive"))
      (node (ref "C5") (pin "2") (pinfunction "2_2") (pintype "passive"))
      (node (ref "C6") (pin "1") (pinfunction "1_1") (pintype "passive"))
      (node (ref "C7") (pin "2") (pinfunction "2_2") (pintype "passive"))
      (node (ref "DC1") (pin "7") (pinfunction "-VOUT_7") (pintype "passive"))
      (node (ref "IC1") (pin "2") (pinfunction "GND_2") (pintype "input"))
      (node (ref "IC10") (pin "2") (pinfunction "C_2") (pintype "passive"))
      (node (ref "IC10") (pin "4") (pinfunction "C_4") (pintype "passive"))
      (node (ref "IC10") (pin "6") (pinfunction "C_6") (pintype "passive"))
      (node (ref "IC10") (pin "9") (pinfunction "EMIT_9") (pintype "passive"))
      (node (ref "IC11") (pin "2") (pinfunction "C_2") (pintype "passive"))
      (node (ref "IC11") (pin "4") (pinfunction "C_4") (pintype "passive"))
      (node (ref "IC4") (pin "11") (pinfunction "GND_11") (pintype "power_in"))
      (node (ref "IC4") (pin "31") (pinfunction "GND_31") (pintype "power_in"))
      (node (ref "LED12") (pin "K") (pinfunction "C_K") (pintype "passive"))
      (node (ref "R1") (pin "2") (pinfunction "2_2") (pintype "passive"))
      (node (ref "R11") (pin "1") (pinfunction "1_1") (pintype "passive"))
      (node (ref "R12") (pin "2") (pinfunction "2_2") (pintype "passive"))
      (node (ref "R13") (pin "2") (pinfunction "2_2") (pintype "passive"))
      (node (ref "R14") (pin "2") (pinfunction "2_2") (pintype "passive"))
      (node (ref "R2") (pin "2") (pinfunction "2_2") (pintype "passive"))
      (node (ref "R3") (pin "2") (pinfunction "2_2") (pintype "passive"))
      (node (ref "R4") (pin "2") (pinfunction "2_2") (pintype "passive"))
      (node (ref "R5") (pin "2") (pinfunction "2_2") (pintype "passive"))
      (node (ref "R6") (pin "2") (pinfunction "2_2") (pintype "passive"))
      (node (ref "R7") (pin "2") (pinfunction "2_2") (pintype "passive"))
      (node (ref "R8") (pin "2") (pinfunction "2_2") (pintype "passive"))
      (node (ref "SV1") (pin "10") (pinfunction "10_10") (pintype "passive"))
      (node (ref "SV1") (pin "4") (pinfunction "4_4") (pintype "passive"))
      (node (ref "SV1") (pin "6") (pinfunction "6_6") (pintype "passive"))
      (node (ref "SV1") (pin "8") (pinfunction "8_8") (pintype "passive"))
      (node (ref "U$2") (pin "4") (pinfunction "POTI_-_4") (pintype "power_in"))
      (node (ref "U$3") (pin "10") (pinfunction "GND_10") (pintype "power_in"))
      (node (ref "U$3") (pin "12") (pinfunction "GND_12") (pintype "power_in"))
      (node (ref "U$3") (pin "14") (pinfunction "GND_14") (pintype "power_in"))
      (node (ref "U$3") (pin "4") (pinfunction "GND_4") (pintype "power_in"))
      (node (ref "U$3") (pin "6") (pinfunction "GND_6") (pintype "power_in"))
      (node (ref "U$3") (pin "8") (pinfunction "GND_8") (pintype "power_in"))
      (node (ref "X1") (pin "1") (pinfunction "1_1") (pintype "passive"))
      (node (ref "X1") (pin "5") (pinfunction "5_5") (pintype "passive"))
    )
    (net (code "18") (name "GYRO_REF") (class "Default")
      (node (ref "C15") (pin "1") (pinfunction "1_1") (pintype "passive"))
      (node (ref "IC4") (pin "35") (pinfunction "(ADC5)PA5_35") (pintype "bidirectional"))
      (node (ref "U$3") (pin "11") (pinfunction "GYRO_REF_11") (pintype "output"))
    )
    (net (code "19") (name "GYRO_X") (class "Default")
      (node (ref "C13") (pin "1") (pinfunction "1_1") (pintype "passive"))
      (node (ref "IC4") (pin "33") (pinfunction "(ADC7)PA7_33") (pintype "bidirectional"))
      (node (ref "U$3") (pin "13") (pinfunction "GYRO_X_13") (pintype "output"))
    )
    (net (code "20") (name "GYRO_Y") (class "Default")
      (node (ref "C14") (pin "1") (pinfunction "1_1") (pintype "passive"))
      (node (ref "IC4") (pin "34") (pinfunction "(ADC6)PA6_34") (pintype "bidirectional"))
      (node (ref "U$3") (pin "9") (pinfunction "GYRO_Y_9") (pintype "output"))
    )
    (net (code "21") (name "MISO") (class "Default")
      (node (ref "IC4") (pin "7") (pinfunction "(MISO)PB6_7") (pintype "bidirectional"))
      (node (ref "SV1") (pin "9") (pinfunction "9_9") (pintype "passive"))
    )
    (net (code "22") (name "MOSI") (class "Default")
      (node (ref "IC4") (pin "6") (pinfunction "(MOSI)PB5_6") (pintype "bidirectional"))
      (node (ref "SV1") (pin "1") (pinfunction "1_1") (pintype "passive"))
    )
    (net (code "23") (name "MOTOR_PWM_LST") (class "Default")
      (node (ref "LEISTUNG") (pin "2") (pinfunction "S_2") (pintype "passive"))
      (node (ref "LEISTUNG") (pin "4") (pinfunction "S_4") (pintype "passive"))
    )
    (net (code "24") (name "MOTOR_PWM_L_CTL") (class "Default")
      (node (ref "IC4") (pin "19") (pinfunction "(OC1A)PD5_19") (pintype "bidirectional"))
      (node (ref "Q2") (pin "2") (pinfunction "G_2") (pintype "passive"))
      (node (ref "R26") (pin "1") (pinfunction "1_1") (pintype "passive"))
    )
    (net (code "25") (name "MOTOR_PWM_L_LST") (class "Default")
      (node (ref "IC11") (pin "16") (pinfunction "COL_16") (pintype "passive"))
      (node (ref "R32") (pin "2") (pinfunction "2_2") (pintype "passive"))
    )
    (net (code "26") (name "MOTOR_PWM_R_CTL") (class "Default")
      (node (ref "IC4") (pin "18") (pinfunction "(OC1B)PD4_18") (pintype "bidirectional"))
      (node (ref "Q3") (pin "2") (pinfunction "G_2") (pintype "passive"))
      (node (ref "R27") (pin "1") (pinfunction "1_1") (pintype "passive"))
    )
    (net (code "27") (name "MOTOR_PWM_R_LST") (class "Default")
      (node (ref "IC11") (pin "14") (pinfunction "COL_14") (pintype "passive"))
      (node (ref "R33") (pin "2") (pinfunction "2_2") (pintype "passive"))
    )
    (net (code "28") (name "NC") (class "Default")
      (node (ref "LEISTUNG") (pin "10") (pinfunction "S_10") (pintype "passive"))
    )
    (net (code "29") (name "Net-(IC3A-C1+)") (class "Default")
      (node (ref "C8") (pin "+") (pinfunction "+_+") (pintype "passive"))
      (node (ref "IC3") (pin "1") (pinfunction "C1+_1") (pintype "bidirectional"))
    )
    (net (code "30") (name "Net-(IC3A-C1-)") (class "Default")
      (node (ref "C8") (pin "-") (pinfunction "-_-") (pintype "passive"))
      (node (ref "IC3") (pin "3") (pinfunction "C1-_3") (pintype "bidirectional"))
    )
    (net (code "31") (name "Net-(IC3A-C2+)") (class "Default")
      (node (ref "C9") (pin "+") (pinfunction "+_+") (pintype "passive"))
      (node (ref "IC3") (pin "4") (pinfunction "C2+_4") (pintype "bidirectional"))
    )
    (net (code "32") (name "Net-(IC3A-V+)") (class "Default")
      (node (ref "C10") (pin "+") (pinfunction "+_+") (pintype "passive"))
      (node (ref "IC3") (pin "2") (pinfunction "V+_2") (pintype "bidirectional"))
    )
    (net (code "33") (name "Net-(IC3A-V-)") (class "Default")
      (node (ref "C11") (pin "-") (pinfunction "-_-") (pintype "passive"))
      (node (ref "IC3") (pin "6") (pinfunction "V-_6") (pintype "bidirectional"))
    )
    (net (code "34") (name "Net-(IC4-(OC2)PD7)") (class "Default")
      (node (ref "C5") (pin "1") (pinfunction "1_1") (pintype "passive"))
      (node (ref "IC4") (pin "21") (pinfunction "(OC2)PD7_21") (pintype "bidirectional"))
      (node (ref "R10") (pin "1") (pinfunction "1_1") (pintype "passive"))
    )
    (net (code "35") (name "Net-(IC4-XTAL1)") (class "Default")
      (node (ref "C1") (pin "1") (pinfunction "1_1") (pintype "passive"))
      (node (ref "IC4") (pin "13") (pinfunction "XTAL1_13") (pintype "bidirectional"))
      (node (ref "Q1") (pin "2") (pinfunction "2_2") (pintype "passive"))
    )
    (net (code "36") (name "Net-(IC4-XTAL2)") (class "Default")
      (node (ref "C2") (pin "1") (pinfunction "1_1") (pintype "passive"))
      (node (ref "IC4") (pin "12") (pinfunction "XTAL2_12") (pintype "bidirectional"))
      (node (ref "Q1") (pin "1") (pinfunction "1_1") (pintype "passive"))
    )
    (net (code "37") (name "Net-(IC10A-A)") (class "Default")
      (node (ref "IC10") (pin "1") (pinfunction "A_1") (pintype "passive"))
      (node (ref "R15") (pin "2") (pinfunction "2_2") (pintype "passive"))
    )
    (net (code "38") (name "Net-(IC10B-A)") (class "Default")
      (node (ref "IC10") (pin "3") (pinfunction "A_3") (pintype "passive"))
      (node (ref "R16") (pin "2") (pinfunction "2_2") (pintype "passive"))
    )
    (net (code "39") (name "Net-(IC10C-A)") (class "Default")
      (node (ref "IC10") (pin "5") (pinfunction "A_5") (pintype "passive"))
      (node (ref "R17") (pin "2") (pinfunction "2_2") (pintype "passive"))
    )
    (net (code "40") (name "Net-(IC10D-A)") (class "Default")
      (node (ref "IC10") (pin "7") (pinfunction "A_7") (pintype "passive"))
      (node (ref "R25") (pin "2") (pinfunction "2_2") (pintype "passive"))
    )
    (net (code "41") (name "Net-(IC11A-A)") (class "Default")
      (node (ref "IC11") (pin "1") (pinfunction "A_1") (pintype "passive"))
      (node (ref "R26") (pin "2") (pinfunction "2_2") (pintype "passive"))
    )
    (net (code "42") (name "Net-(IC11B-A)") (class "Default")
      (node (ref "IC11") (pin "3") (pinfunction "A_3") (pintype "passive"))
      (node (ref "R27") (pin "2") (pinfunction "2_2") (pintype "passive"))
    )
    (net (code "43") (name "Net-(JP1-Pad2)") (class "Default")
      (node (ref "JP1") (pin "2") (pinfunction "2_2") (pintype "passive"))
      (node (ref "X1") (pin "9") (pinfunction "9_9") (pintype "passive"))
    )
    (net (code "44") (name "Net-(LED1-C)") (class "Default")
      (node (ref "LED1") (pin "K") (pinfunction "C_K") (pintype "passive"))
      (node (ref "R3") (pin "1") (pinfunction "1_1") (pintype "passive"))
    )
    (net (code "45") (name "Net-(LED2-C)") (class "Default")
      (node (ref "LED2") (pin "K") (pinfunction "C_K") (pintype "passive"))
      (node (ref "R2") (pin "1") (pinfunction "1_1") (pintype "passive"))
    )
    (net (code "46") (name "Net-(LED3-C)") (class "Default")
      (node (ref "LED3") (pin "K") (pinfunction "C_K") (pintype "passive"))
      (node (ref "R1") (pin "1") (pinfunction "1_1") (pintype "passive"))
    )
    (net (code "47") (name "Net-(LED4-C)") (class "Default")
      (node (ref "LED4") (pin "K") (pinfunction "C_K") (pintype "passive"))
      (node (ref "R4") (pin "1") (pinfunction "1_1") (pintype "passive"))
    )
    (net (code "48") (name "Net-(LED5-C)") (class "Default")
      (node (ref "LED5") (pin "K") (pinfunction "C_K") (pintype "passive"))
      (node (ref "R5") (pin "1") (pinfunction "1_1") (pintype "passive"))
    )
    (net (code "49") (name "Net-(LED6-C)") (class "Default")
      (node (ref "LED6") (pin "K") (pinfunction "C_K") (pintype "passive"))
      (node (ref "R6") (pin "1") (pinfunction "1_1") (pintype "passive"))
    )
    (net (code "50") (name "Net-(LED7-C)") (class "Default")
      (node (ref "LED7") (pin "K") (pinfunction "C_K") (pintype "passive"))
      (node (ref "R7") (pin "1") (pinfunction "1_1") (pintype "passive"))
    )
    (net (code "51") (name "Net-(LED8-C)") (class "Default")
      (node (ref "LED8") (pin "K") (pinfunction "C_K") (pintype "passive"))
      (node (ref "R8") (pin "1") (pinfunction "1_1") (pintype "passive"))
    )
    (net (code "52") (name "Net-(LED9-C)") (class "Default")
      (node (ref "LED9") (pin "K") (pinfunction "C_K") (pintype "passive"))
      (node (ref "R12") (pin "1") (pinfunction "1_1") (pintype "passive"))
    )
    (net (code "53") (name "Net-(LED10-C)") (class "Default")
      (node (ref "LED10") (pin "K") (pinfunction "C_K") (pintype "passive"))
      (node (ref "R13") (pin "1") (pinfunction "1_1") (pintype "passive"))
    )
    (net (code "54") (name "Net-(LED11-C)") (class "Default")
      (node (ref "LED11") (pin "K") (pinfunction "C_K") (pintype "passive"))
      (node (ref "R14") (pin "1") (pinfunction "1_1") (pintype "passive"))
    )
    (net (code "55") (name "Net-(LED12-PadA)") (class "Default")
      (node (ref "LED12") (pin "A") (pinfunction "A_A") (pintype "passive"))
      (node (ref "R34") (pin "1") (pinfunction "1_1") (pintype "passive"))
    )
    (net (code "56") (name "Net-(Q2-D)") (class "Default")
      (node (ref "Q2") (pin "3") (pinfunction "D_3") (pintype "passive"))
      (node (ref "SJ1") (pin "1") (pinfunction "1_1") (pintype "passive"))
    )
    (net (code "57") (name "Net-(Q2-S)") (class "Default")
      (node (ref "LED4") (pin "A") (pinfunction "A_A") (pintype "passive"))
      (node (ref "Q2") (pin "1") (pinfunction "S_1") (pintype "passive"))
    )
    (net (code "58") (name "Net-(Q3-D)") (class "Default")
      (node (ref "Q3") (pin "3") (pinfunction "D_3") (pintype "passive"))
      (node (ref "SJ2") (pin "1") (pinfunction "1_1") (pintype "passive"))
    )
    (net (code "59") (name "Net-(Q3-S)") (class "Default")
      (node (ref "LED5") (pin "A") (pinfunction "A_A") (pintype "passive"))
      (node (ref "Q3") (pin "1") (pinfunction "S_1") (pintype "passive"))
    )
    (net (code "60") (name "Net-(Q4-D)") (class "Default")
      (node (ref "Q4") (pin "3") (pinfunction "D_3") (pintype "passive"))
      (node (ref "SJ3") (pin "1") (pinfunction "1_1") (pintype "passive"))
    )
    (net (code "61") (name "Net-(Q4-S)") (class "Default")
      (node (ref "LED6") (pin "A") (pinfunction "A_A") (pintype "passive"))
      (node (ref "Q4") (pin "1") (pinfunction "S_1") (pintype "passive"))
    )
    (net (code "62") (name "Net-(Q5-D)") (class "Default")
      (node (ref "Q5") (pin "3") (pinfunction "D_3") (pintype "passive"))
      (node (ref "SJ4") (pin "1") (pinfunction "1_1") (pintype "passive"))
    )
    (net (code "63") (name "Net-(Q5-S)") (class "Default")
      (node (ref "LED7") (pin "A") (pinfunction "A_A") (pintype "passive"))
      (node (ref "Q5") (pin "1") (pinfunction "S_1") (pintype "passive"))
    )
    (net (code "64") (name "Net-(Q6-D)") (class "Default")
      (node (ref "Q6") (pin "3") (pinfunction "D_3") (pintype "passive"))
      (node (ref "SJ5") (pin "1") (pinfunction "1_1") (pintype "passive"))
    )
    (net (code "65") (name "Net-(Q6-S)") (class "Default")
      (node (ref "LED8") (pin "A") (pinfunction "A_A") (pintype "passive"))
      (node (ref "Q6") (pin "1") (pinfunction "S_1") (pintype "passive"))
    )
    (net (code "66") (name "Net-(Q7-D)") (class "Default")
      (node (ref "Q7") (pin "3") (pinfunction "D_3") (pintype "passive"))
      (node (ref "SJ6") (pin "1") (pinfunction "1_1") (pintype "passive"))
    )
    (net (code "67") (name "Net-(Q7-S)") (class "Default")
      (node (ref "LED9") (pin "A") (pinfunction "A_A") (pintype "passive"))
      (node (ref "Q7") (pin "1") (pinfunction "S_1") (pintype "passive"))
    )
    (net (code "68") (name "Net-(Q8-D)") (class "Default")
      (node (ref "Q8") (pin "3") (pinfunction "D_3") (pintype "passive"))
      (node (ref "SJ7") (pin "1") (pinfunction "1_1") (pintype "passive"))
    )
    (net (code "69") (name "Net-(Q8-S)") (class "Default")
      (node (ref "LED10") (pin "A") (pinfunction "A_A") (pintype "passive"))
      (node (ref "Q8") (pin "1") (pinfunction "S_1") (pintype "passive"))
    )
    (net (code "70") (name "Net-(Q9-D)") (class "Default")
      (node (ref "Q9") (pin "3") (pinfunction "D_3") (pintype "passive"))
      (node (ref "SJ8") (pin "1") (pinfunction "1_1") (pintype "passive"))
    )
    (net (code "71") (name "Net-(Q9-S)") (class "Default")
      (node (ref "LED11") (pin "A") (pinfunction "A_A") (pintype "passive"))
      (node (ref "Q9") (pin "1") (pinfunction "S_1") (pintype "passive"))
    )
    (net (code "72") (name "POTI") (class "Default")
      (node (ref "C12") (pin "1") (pinfunction "1_1") (pintype "passive"))
      (node (ref "IC4") (pin "39") (pinfunction "(ADC1)PA1_39") (pintype "bidirectional"))
      (node (ref "U$2") (pin "2") (pinfunction "POTI_CONTACT_2") (pintype "output"))
    )
    (net (code "73") (name "RESET") (class "Default")
      (node (ref "C6") (pin "2") (pinfunction "2_2") (pintype "passive"))
      (node (ref "IC4") (pin "9") (pinfunction "RESET_9") (pintype "input"))
      (node (ref "R9") (pin "2") (pinfunction "2_2") (pintype "passive"))
      (node (ref "SV1") (pin "5") (pinfunction "5_5") (pintype "passive"))
    )
    (net (code "74") (name "RS232RX") (class "Default")
      (node (ref "IC3") (pin "14") (pinfunction "T1OUT_14") (pintype "output"))
      (node (ref "JP2") (pin "1") (pinfunction "1_1") (pintype "passive"))
      (node (ref "JP2") (pin "6") (pinfunction "6_6") (pintype "passive"))
    )
    (net (code "75") (name "RS232RX_CON") (class "Default")
      (node (ref "JP2") (pin "3") (pinfunction "3_3") (pintype "passive"))
      (node (ref "X1") (pin "3") (pinfunction "3_3") (pintype "passive"))
    )
    (net (code "76") (name "RS232TX") (class "Default")
      (node (ref "IC3") (pin "13") (pinfunction "R1IN_13") (pintype "input"))
      (node (ref "JP2") (pin "2") (pinfunction "2_2") (pintype "passive"))
      (node (ref "JP2") (pin "5") (pinfunction "5_5") (pintype "passive"))
    )
    (net (code "77") (name "RS232TX_CON") (class "Default")
      (node (ref "JP2") (pin "4") (pinfunction "4_4") (pintype "passive"))
      (node (ref "X1") (pin "4") (pinfunction "4_4") (pintype "passive"))
    )
    (net (code "78") (name "RXD") (class "Default")
      (node (ref "IC3") (pin "12") (pinfunction "R1OUT_12") (pintype "output"))
      (node (ref "IC4") (pin "14") (pinfunction "(RXD)PD0_14") (pintype "bidirectional"))
    )
    (net (code "79") (name "SCK") (class "Default")
      (node (ref "IC4") (pin "8") (pinfunction "(SCK)PB7_8") (pintype "bidirectional"))
      (node (ref "SV1") (pin "7") (pinfunction "7_7") (pintype "passive"))
    )
    (net (code "80") (name "STATUS_LED1") (class "Default")
      (node (ref "IC4") (pin "2") (pinfunction "(T1)PB1_2") (pintype "bidirectional"))
      (node (ref "LED1") (pin "A") (pinfunction "A_A") (pintype "passive"))
    )
    (net (code "81") (name "STATUS_LED2") (class "Default")
      (node (ref "IC4") (pin "3") (pinfunction "(AIN0/INT2)PB2_3") (pintype "bidirectional"))
      (node (ref "LED2") (pin "A") (pinfunction "A_A") (pintype "passive"))
    )
    (net (code "82") (name "STATUS_LED3") (class "Default")
      (node (ref "IC4") (pin "4") (pinfunction "(AIN1/OC0)PB3_4") (pintype "bidirectional"))
      (node (ref "LED3") (pin "A") (pinfunction "A_A") (pintype "passive"))
    )
    (net (code "83") (name "TXD") (class "Default")
      (node (ref "C9") (pin "-") (pinfunction "-_-") (pintype "passive"))
      (node (ref "IC3") (pin "11") (pinfunction "T1IN_11") (pintype "input"))
      (node (ref "IC3") (pin "5") (pinfunction "C2-_5") (pintype "bidirectional"))
      (node (ref "IC4") (pin "15") (pinfunction "(TXD)PD1_15") (pintype "bidirectional"))
    )
    (net (code "84") (name "unconnected-(DC1-ON{slash}OFF-Pad3)") (class "Default")
      (node (ref "DC1") (pin "3") (pinfunction "ON/OFF_3") (pintype "passive"))
    )
    (net (code "85") (name "unconnected-(IC3A-R2IN-Pad8)") (class "Default")
      (node (ref "IC3") (pin "8") (pinfunction "R2IN_8") (pintype "input"))
    )
    (net (code "86") (name "unconnected-(IC3A-R2OUT-Pad9)") (class "Default")
      (node (ref "IC3") (pin "9") (pinfunction "R2OUT_9") (pintype "output"))
    )
    (net (code "87") (name "unconnected-(IC3A-T2IN-Pad10)") (class "Default")
      (node (ref "IC3") (pin "10") (pinfunction "T2IN_10") (pintype "input"))
    )
    (net (code "88") (name "unconnected-(IC3A-T2OUT-Pad7)") (class "Default")
      (node (ref "IC3") (pin "7") (pinfunction "T2OUT_7") (pintype "output"))
    )
    (net (code "89") (name "unconnected-(IC4-(ADC0)PA0-Pad40)") (class "Default")
      (node (ref "IC4") (pin "40") (pinfunction "(ADC0)PA0_40") (pintype "bidirectional"))
    )
    (net (code "90") (name "unconnected-(IC4-(ADC2)PA2-Pad38)") (class "Default")
      (node (ref "IC4") (pin "38") (pinfunction "(ADC2)PA2_38") (pintype "bidirectional"))
    )
    (net (code "91") (name "unconnected-(IC4-(INT0)PD2-Pad16)") (class "Default")
      (node (ref "IC4") (pin "16") (pinfunction "(INT0)PD2_16") (pintype "bidirectional"))
    )
    (net (code "92") (name "unconnected-(IC4-(SCL)PC0-Pad22)") (class "Default")
      (node (ref "IC4") (pin "22") (pinfunction "(SCL)PC0_22") (pintype "bidirectional"))
    )
    (net (code "93") (name "unconnected-(IC4-(SDA)PC1-Pad23)") (class "Default")
      (node (ref "IC4") (pin "23") (pinfunction "(SDA)PC1_23") (pintype "bidirectional"))
    )
    (net (code "94") (name "unconnected-(IC4-(SS)PB4-Pad5)") (class "Default")
      (node (ref "IC4") (pin "5") (pinfunction "(SS)PB4_5") (pintype "bidirectional"))
    )
    (net (code "95") (name "unconnected-(IC4-(T0{slash}XCK)PB0-Pad1)") (class "Default")
      (node (ref "IC4") (pin "1") (pinfunction "(T0/XCK)PB0_1") (pintype "bidirectional"))
    )
    (net (code "96") (name "unconnected-(IC4-(TDI)PC5-Pad27)") (class "Default")
      (node (ref "IC4") (pin "27") (pinfunction "(TDI)PC5_27") (pintype "bidirectional"))
    )
    (net (code "97") (name "unconnected-(IC4-(TMS)PC3-Pad25)") (class "Default")
      (node (ref "IC4") (pin "25") (pinfunction "(TMS)PC3_25") (pintype "bidirectional"))
    )
    (net (code "98") (name "unconnected-(IC4-(TOSC1)PC6-Pad28)") (class "Default")
      (node (ref "IC4") (pin "28") (pinfunction "(TOSC1)PC6_28") (pintype "bidirectional"))
    )
    (net (code "99") (name "unconnected-(SV1-Pad3)") (class "Default")
      (node (ref "SV1") (pin "3") (pinfunction "3_3") (pintype "passive"))
    )
    (net (code "100") (name "unconnected-(X1-Pad2)") (class "Default")
      (node (ref "X1") (pin "2") (pinfunction "2_2") (pintype "passive"))
    )
    (net (code "101") (name "unconnected-(X1-Pad6)") (class "Default")
      (node (ref "X1") (pin "6") (pinfunction "6_6") (pintype "passive"))
    )
    (net (code "102") (name "unconnected-(X1-Pad7)") (class "Default")
      (node (ref "X1") (pin "7") (pinfunction "7_7") (pintype "passive"))
    )
    (net (code "103") (name "unconnected-(X1-Pad8)") (class "Default")
      (node (ref "X1") (pin "8") (pinfunction "8_8") (pintype "passive"))
    )
  )
)
